# 243-436_Manette-ESP32.net
KiCad netlist of a schematic drawn in Altium Designer
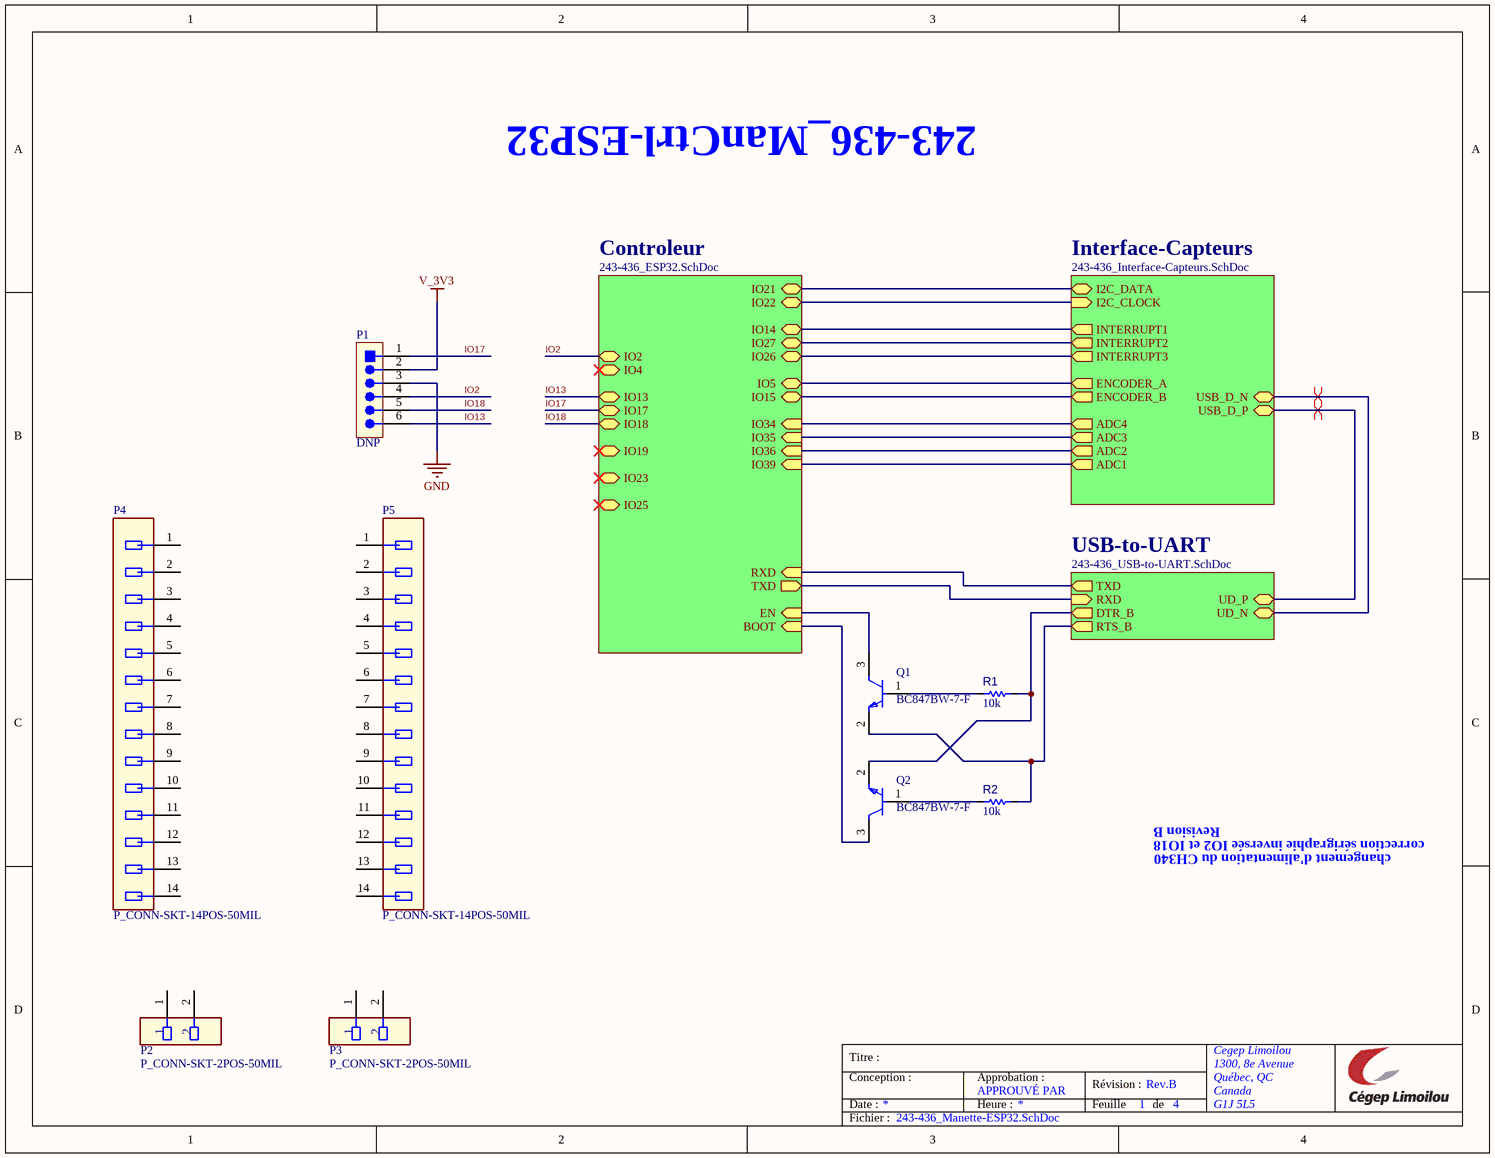
[diagram p0: 243-436_Manette-ESP32.SchDoc]

(export (version "E")
  (design (tool "Eeschema 10.0.6"))
  (components
    (comp (ref "P1")
      (value "DNP")
      (footprint "P_CONN_HDR_1ROW_6POS_100MIL")
      (description "Conn. Header 6pos 100mils")
      (libsource (lib "243-336_MP_Manette") (part "P_Conn_01x06_100mils"))
    )
    (comp (ref "P2")
      (value "P_CONN-SKT-2POS-50MIL")
      (footprint "P_CONN_SKT_1ROW_2POS_50MIL")
      (description "CONN SOCKET 2POS 1.27mm SINGLE ROW TH")
      (libsource (lib "243-436_MP_Man-ESP32") (part "P_CONN-SKT-2POS-50MIL"))
    )
    (comp (ref "P3")
      (value "P_CONN-SKT-2POS-50MIL")
      (footprint "P_CONN_SKT_1ROW_2POS_50MIL")
      (description "CONN SOCKET 2POS 1.27mm SINGLE ROW TH")
      (libsource (lib "243-436_MP_Man-ESP32") (part "P_CONN-SKT-2POS-50MIL"))
    )
    (comp (ref "P4")
      (value "P_CONN-SKT-14POS-50MIL")
      (footprint "P_CONN_SKT_1ROW_14POS_50MIL")
      (description "CONN SOCKET 14POS 1.27mm SINGLE ROW TH")
      (libsource (lib "") (part "P_CONN-SKT-14POS-50MIL_1"))
    )
    (comp (ref "P5")
      (value "P_CONN-SKT-14POS-50MIL")
      (footprint "P_CONN_SKT_1ROW_14POS_50MIL")
      (description "CONN SOCKET 14POS 1.27mm SINGLE ROW TH")
      (libsource (lib "243-436_MP_Man-ESP32") (part "P_CONN-SKT-14POS-50MIL"))
    )
    (comp (ref "Q1")
      (value "BC847BW-7-F")
      (footprint "SOT323-IPC_B")
      (description "TRANS NPN 45V 0.1A SC70-3")
      (libsource (lib "TEP-AltiumLib-Discretes") (part "Q_BC847BW"))
    )
    (comp (ref "Q2")
      (value "BC847BW-7-F")
      (footprint "SOT323-IPC_B")
      (description "TRANS NPN 45V 0.1A SC70-3")
      (libsource (lib "TEP-AltiumLib-Discretes") (part "Q_BC847BW"))
    )
    (comp (ref "R1")
      (value "10k")
      (footprint "R_1005[0402]")
      (description "Resistor type 1")
      (fields (field (name "TOLERANCE") "1%") (field (name "Comment") "Res 10k 1% 0402"))
      (libsource (lib "TEP_243-Altium_DBLib") (part "resistor"))
    )
    (comp (ref "R2")
      (value "10k")
      (footprint "R_1005[0402]")
      (description "Resistor type 1")
      (fields (field (name "TOLERANCE") "1%") (field (name "Comment") "Res 10k 1% 0402"))
      (libsource (lib "TEP_243-Altium_DBLib") (part "resistor"))
    )
  )
  (nets
    (net (code "5") (name "/BOOT") (class "Default")
      (node (ref "Q2") (pin "3") (pinfunction "C_3") (pintype "passive"))
    )
    (net (code "6") (name "/DTR_B") (class "Default")
      (node (ref "Q2") (pin "2") (pinfunction "E_2") (pintype "passive"))
      (node (ref "R1") (pin "1") (pinfunction "1_1") (pintype "passive"))
    )
    (net (code "7") (name "/EN") (class "Default")
      (node (ref "Q1") (pin "3") (pinfunction "C_3") (pintype "passive"))
    )
    (net (code "15") (name "/IO2") (class "Default")
      (node (ref "P1") (pin "4") (pinfunction "4_4") (pintype "passive"))
    )
    (net (code "17") (name "/IO13") (class "Default")
      (node (ref "P1") (pin "6") (pinfunction "6_6") (pintype "passive"))
    )
    (net (code "18") (name "/IO17") (class "Default")
      (node (ref "P1") (pin "1") (pinfunction "1_1") (pintype "passive"))
    )
    (net (code "19") (name "/IO18") (class "Default")
      (node (ref "P1") (pin "5") (pinfunction "5_5") (pintype "passive"))
    )
    (net (code "23") (name "/RTS_B") (class "Default")
      (node (ref "Q1") (pin "2") (pinfunction "E_2") (pintype "passive"))
      (node (ref "R2") (pin "1") (pinfunction "1_1") (pintype "passive"))
    )
    (net (code "28") (name "GND") (class "Default")
      (node (ref "P1") (pin "3") (pinfunction "3_3") (pintype "passive"))
    )
    (net (code "29") (name "Net-(Q1-B)") (class "Default")
      (node (ref "Q1") (pin "1") (pinfunction "B_1") (pintype "passive"))
      (node (ref "R1") (pin "2") (pinfunction "2_2") (pintype "passive"))
    )
    (net (code "30") (name "Net-(Q2-B)") (class "Default")
      (node (ref "Q2") (pin "1") (pinfunction "B_1") (pintype "passive"))
      (node (ref "R2") (pin "2") (pinfunction "2_2") (pintype "passive"))
    )
    (net (code "31") (name "V_3V3") (class "Default")
      (node (ref "P1") (pin "2") (pinfunction "2_2") (pintype "passive"))
    )
    (net (code "32") (name "unconnected-(P2-Pad1)") (class "Default")
      (node (ref "P2") (pin "1") (pinfunction "1_1") (pintype "passive"))
    )
    (net (code "33") (name "unconnected-(P2-Pad2)") (class "Default")
      (node (ref "P2") (pin "2") (pinfunction "2_2") (pintype "passive"))
    )
    (net (code "34") (name "unconnected-(P3-Pad1)") (class "Default")
      (node (ref "P3") (pin "1") (pinfunction "1_1") (pintype "passive"))
    )
    (net (code "35") (name "unconnected-(P3-Pad2)") (class "Default")
      (node (ref "P3") (pin "2") (pinfunction "2_2") (pintype "passive"))
    )
    (net (code "36") (name "unconnected-(P4-Pad1)") (class "Default")
      (node (ref "P4") (pin "1") (pinfunction "1_1") (pintype "passive"))
    )
    (net (code "37") (name "unconnected-(P4-Pad2)") (class "Default")
      (node (ref "P4") (pin "2") (pinfunction "2_2") (pintype "passive"))
    )
    (net (code "38") (name "unconnected-(P4-Pad3)") (class "Default")
      (node (ref "P4") (pin "3") (pinfunction "3_3") (pintype "passive"))
    )
    (net (code "39") (name "unconnected-(P4-Pad4)") (class "Default")
      (node (ref "P4") (pin "4") (pinfunction "4_4") (pintype "passive"))
    )
    (net (code "40") (name "unconnected-(P4-Pad5)") (class "Default")
      (node (ref "P4") (pin "5") (pinfunction "5_5") (pintype "passive"))
    )
    (net (code "41") (name "unconnected-(P4-Pad6)") (class "Default")
      (node (ref "P4") (pin "6") (pinfunction "6_6") (pintype "passive"))
    )
    (net (code "42") (name "unconnected-(P4-Pad7)") (class "Default")
      (node (ref "P4") (pin "7") (pinfunction "7_7") (pintype "passive"))
    )
    (net (code "43") (name "unconnected-(P4-Pad8)") (class "Default")
      (node (ref "P4") (pin "8") (pinfunction "8_8") (pintype "passive"))
    )
    (net (code "44") (name "unconnected-(P4-Pad9)") (class "Default")
      (node (ref "P4") (pin "9") (pinfunction "9_9") (pintype "passive"))
    )
    (net (code "45") (name "unconnected-(P4-Pad10)") (class "Default")
      (node (ref "P4") (pin "10") (pinfunction "10_10") (pintype "passive"))
    )
    (net (code "46") (name "unconnected-(P4-Pad11)") (class "Default")
      (node (ref "P4") (pin "11") (pinfunction "11_11") (pintype "passive"))
    )
    (net (code "47") (name "unconnected-(P4-Pad12)") (class "Default")
      (node (ref "P4") (pin "12") (pinfunction "12_12") (pintype "passive"))
    )
    (net (code "48") (name "unconnected-(P4-Pad13)") (class "Default")
      (node (ref "P4") (pin "13") (pinfunction "13_13") (pintype "passive"))
    )
    (net (code "49") (name "unconnected-(P4-Pad14)") (class "Default")
      (node (ref "P4") (pin "14") (pinfunction "14_14") (pintype "passive"))
    )
    (net (code "50") (name "unconnected-(P5-Pad1)") (class "Default")
      (node (ref "P5") (pin "1") (pinfunction "1_1") (pintype "passive"))
    )
    (net (code "51") (name "unconnected-(P5-Pad2)") (class "Default")
      (node (ref "P5") (pin "2") (pinfunction "2_2") (pintype "passive"))
    )
    (net (code "52") (name "unconnected-(P5-Pad3)") (class "Default")
      (node (ref "P5") (pin "3") (pinfunction "3_3") (pintype "passive"))
    )
    (net (code "53") (name "unconnected-(P5-Pad4)") (class "Default")
      (node (ref "P5") (pin "4") (pinfunction "4_4") (pintype "passive"))
    )
    (net (code "54") (name "unconnected-(P5-Pad5)") (class "Default")
      (node (ref "P5") (pin "5") (pinfunction "5_5") (pintype "passive"))
    )
    (net (code "55") (name "unconnected-(P5-Pad6)") (class "Default")
      (node (ref "P5") (pin "6") (pinfunction "6_6") (pintype "passive"))
    )
    (net (code "56") (name "unconnected-(P5-Pad7)") (class "Default")
      (node (ref "P5") (pin "7") (pinfunction "7_7") (pintype "passive"))
    )
    (net (code "57") (name "unconnected-(P5-Pad8)") (class "Default")
      (node (ref "P5") (pin "8") (pinfunction "8_8") (pintype "passive"))
    )
    (net (code "58") (name "unconnected-(P5-Pad9)") (class "Default")
      (node (ref "P5") (pin "9") (pinfunction "9_9") (pintype "passive"))
    )
    (net (code "59") (name "unconnected-(P5-Pad10)") (class "Default")
      (node (ref "P5") (pin "10") (pinfunction "10_10") (pintype "passive"))
    )
    (net (code "60") (name "unconnected-(P5-Pad11)") (class "Default")
      (node (ref "P5") (pin "11") (pinfunction "11_11") (pintype "passive"))
    )
    (net (code "61") (name "unconnected-(P5-Pad12)") (class "Default")
      (node (ref "P5") (pin "12") (pinfunction "12_12") (pintype "passive"))
    )
    (net (code "62") (name "unconnected-(P5-Pad13)") (class "Default")
      (node (ref "P5") (pin "13") (pinfunction "13_13") (pintype "passive"))
    )
    (net (code "63") (name "unconnected-(P5-Pad14)") (class "Default")
      (node (ref "P5") (pin "14") (pinfunction "14_14") (pintype "passive"))
    )
  )
)
